# Sheet1.net
KiCad netlist of a schematic drawn in Altium Designer
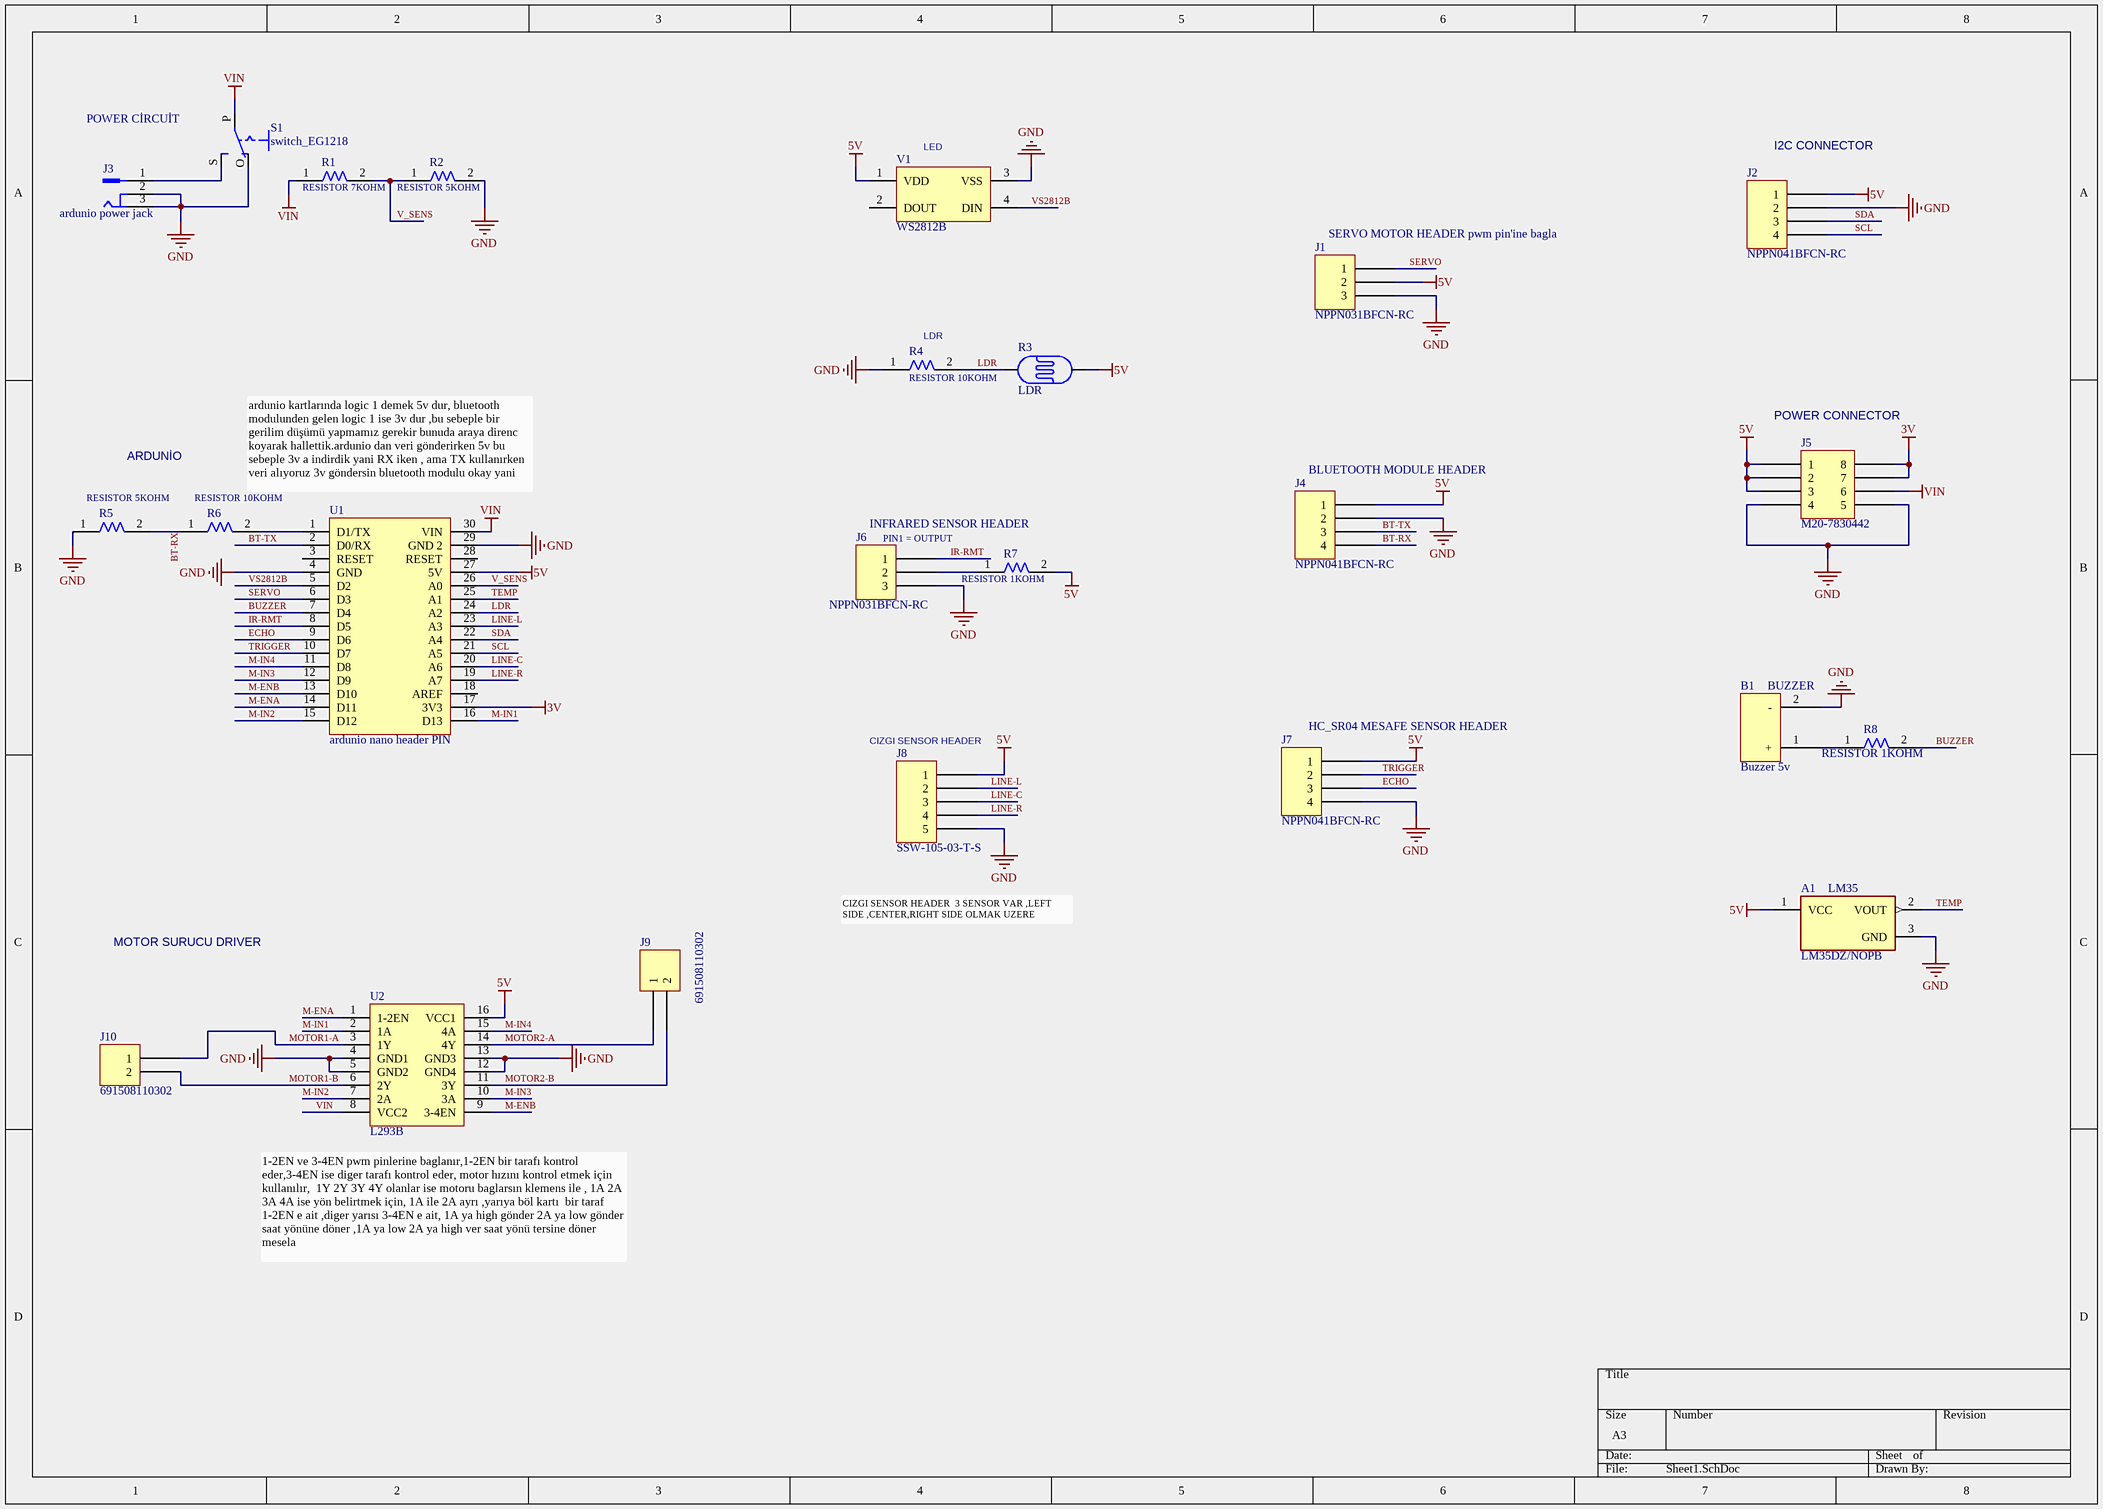
[diagram p0: Sheet1.SchDoc]

(export (version "E")
  (design (tool "Eeschema 10.0.6"))
  (components
    (comp (ref "A1")
      (value "LM35DZ/NOPB")
      (footprint "PcbLib1:LM35DZ_TO92127P521H735-3")
      (description "LM35DZ TEMPERATURE SENSOR")
      (libsource (lib "Schlib1") (part "LM35DZ/NOPB"))
    )
    (comp (ref "B1")
      (value "Buzzer 5v")
      (footprint "Buzzer 5V")
      (libsource (lib "Schlib1") (part "Buzzer 5v"))
    )
    (comp (ref "J1")
      (value "NPPN031BFCN-RC")
      (footprint "SULLINS NPPN031BFCN")
      (description "CONN HDR 3POS 0.079 GOLD PCB")
      (fields (field (name "MANUFACTURER") "Sullins Connector Solutions"))
      (libsource (lib "Celestial Altium Library - altium_library") (part "3 Pin"))
    )
    (comp (ref "J2")
      (value "NPPN041BFCN-RC")
      (footprint "SULLINS NPPN041BFCN")
      (description "CONN HDR 4POS 0.079 GOLD PCB")
      (fields (field (name "MANUFACTURER") "Sullins Connector Solutions"))
      (libsource (lib "Celestial Altium Library - altium_library") (part "4 Pin"))
    )
    (comp (ref "J3")
      (value "ardunio power jack")
      (footprint "ardunio uno power jack")
      (description "CONN PWR JACK 2X5.5MM SOLDER  ,PJ-102AH")
      (libsource (lib "Schlib1") (part "ardunio power jack"))
    )
    (comp (ref "J4")
      (value "NPPN041BFCN-RC")
      (footprint "SULLINS NPPN041BFCN")
      (description "CONN HDR 4POS 0.079 GOLD PCB")
      (fields (field (name "MANUFACTURER") "Sullins Connector Solutions"))
      (libsource (lib "Celestial Altium Library - altium_library") (part "4 Pin"))
    )
    (comp (ref "J5")
      (value "M20-7830442")
      (footprint "HARWIN M20-7830445")
      (description "CONN RCPT 8POS 0.1 GOLD PCB")
      (fields (field (name "MANUFACTURER") "Harwin Inc."))
      (libsource (lib "Celestial Altium Library - altium_library") (part "2X4 PIN DU"))
    )
    (comp (ref "J6")
      (value "NPPN031BFCN-RC")
      (footprint "SULLINS NPPN031BFCN")
      (description "CONN HDR 3POS 0.079 GOLD PCB")
      (fields (field (name "MANUFACTURER") "Sullins Connector Solutions"))
      (libsource (lib "Celestial Altium Library - altium_library") (part "3 Pin"))
    )
    (comp (ref "J7")
      (value "NPPN041BFCN-RC")
      (footprint "SULLINS NPPN041BFCN")
      (description "CONN HDR 4POS 0.079 GOLD PCB")
      (fields (field (name "MANUFACTURER") "Sullins Connector Solutions"))
      (libsource (lib "Celestial Altium Library - altium_library") (part "4 Pin"))
    )
    (comp (ref "J8")
      (value "SSW-105-03-T-S")
      (footprint "SAMTEC SSW-105-03-T-S")
      (description "CONN RCPT 5POS 0.1 TIN PCB")
      (fields (field (name "MANUFACTURER") "Samtec Inc."))
      (libsource (lib "Celestial Altium Library - altium_library") (part "5 Pin"))
    )
    (comp (ref "J9")
      (value "691508110302")
      (footprint "WURTH 691508110302")
      (description "TERM BLOCK 2POS 3.5MM SMD")
      (fields (field (name "MANUFACTURER") "Würth Elektronik") (field (name "VOLTAGE") "300V"))
      (libsource (lib "Celestial Altium Library - altium_library") (part "2 Pin"))
    )
    (comp (ref "J10")
      (value "691508110302")
      (footprint "WURTH 691508110302")
      (description "TERM BLOCK 2POS 3.5MM SMD")
      (fields (field (name "MANUFACTURER") "Würth Elektronik") (field (name "VOLTAGE") "300V"))
      (libsource (lib "") (part "2 Pin_1"))
    )
    (comp (ref "R1")
      (value "RESISTOR 7KOHM")
      (footprint "RES50")
      (libsource (lib "Schlib1") (part "RESISTOR 7KOHM"))
    )
    (comp (ref "R2")
      (value "RESISTOR 5KOHM")
      (footprint "RES50")
      (libsource (lib "Schlib1") (part "RESISTOR 5KOHM"))
    )
    (comp (ref "R3")
      (value "LDR")
      (footprint "PcbLib1:LDR")
      (fields (field (name "MF") "Fairway Electronics"))
      (libsource (lib "Schlib1") (part "LDR"))
    )
    (comp (ref "R4")
      (value "RESISTOR 10KOHM")
      (footprint "RES50")
      (libsource (lib "Schlib1") (part "RESISTOR 10KOHM"))
    )
    (comp (ref "R5")
      (value "RESISTOR 5KOHM")
      (footprint "RES50")
      (libsource (lib "Schlib1") (part "RESISTOR 5KOHM"))
    )
    (comp (ref "R6")
      (value "RESISTOR 10KOHM")
      (footprint "RES50")
      (libsource (lib "Schlib1") (part "RESISTOR 10KOHM"))
    )
    (comp (ref "R7")
      (value "RESISTOR 1KOHM")
      (footprint "RES50")
      (description "RESISTOR 5KOHM")
      (libsource (lib "Schlib1") (part "RESISTOR 5KOHM"))
    )
    (comp (ref "R8")
      (value "RESISTOR 1KOHM")
      (footprint "RES50")
      (description "RESISTOR 5KOHM")
      (libsource (lib "Schlib1") (part "RESISTOR 5KOHM"))
    )
    (comp (ref "S1")
      (value "switch_EG1218")
      (footprint "PcbLib1:EG1218")
      (fields (field (name "MP") "EG1218"))
      (libsource (lib "Schlib1") (part "switch_EG1218"))
    )
    (comp (ref "U1")
      (value "ardunio nano header PIN")
      (footprint "ARDUNIO NANO")
      (description "ardunio nanoheader pin 2x15")
      (libsource (lib "Schlib1") (part "ardunio nanoheader"))
    )
    (comp (ref "U2") (value "L293B") (footprint "L293B-L293D") (libsource (lib "Schlib1") (part "L293B")))
    (comp (ref "V1") (value "WS2812B") (footprint "WS2812B") (libsource (lib "Schlib1") (part "WS2812B")))
  )
  (nets
    (net (code "1") (name "/BT-RX") (class "Default")
      (node (ref "J4") (pin "4") (pinfunction "4_4") (pintype "passive"))
      (node (ref "R5") (pin "2") (pinfunction "2_2") (pintype "passive"))
      (node (ref "R6") (pin "1") (pinfunction "1_1") (pintype "passive"))
    )
    (net (code "2") (name "/BT-TX") (class "Default")
      (node (ref "J4") (pin "3") (pinfunction "3_3") (pintype "passive"))
      (node (ref "U1") (pin "2") (pinfunction "D0/RX_2") (pintype "passive"))
    )
    (net (code "3") (name "/BUZZER") (class "Default")
      (node (ref "R8") (pin "2") (pinfunction "2_2") (pintype "passive"))
      (node (ref "U1") (pin "7") (pinfunction "D4_7") (pintype "passive"))
    )
    (net (code "4") (name "/ECHO") (class "Default")
      (node (ref "J7") (pin "3") (pinfunction "3_3") (pintype "passive"))
      (node (ref "U1") (pin "9") (pinfunction "D6_9") (pintype "passive"))
    )
    (net (code "5") (name "/IR-RMT") (class "Default")
      (node (ref "J6") (pin "1") (pinfunction "1_1") (pintype "passive"))
      (node (ref "U1") (pin "8") (pinfunction "D5_8") (pintype "passive"))
    )
    (net (code "6") (name "/LDR") (class "Default")
      (node (ref "R3") (pin "1") (pinfunction "P$1_1") (pintype "bidirectional"))
      (node (ref "R4") (pin "2") (pinfunction "2_2") (pintype "passive"))
      (node (ref "U1") (pin "24") (pinfunction "A2_24") (pintype "passive"))
    )
    (net (code "7") (name "/LINE-C") (class "Default")
      (node (ref "J8") (pin "3") (pinfunction "3_3") (pintype "passive"))
      (node (ref "U1") (pin "20") (pinfunction "A6_20") (pintype "passive"))
    )
    (net (code "8") (name "/LINE-L") (class "Default")
      (node (ref "J8") (pin "2") (pinfunction "2_2") (pintype "passive"))
      (node (ref "U1") (pin "23") (pinfunction "A3_23") (pintype "passive"))
    )
    (net (code "9") (name "/LINE-R") (class "Default")
      (node (ref "J8") (pin "4") (pinfunction "4_4") (pintype "passive"))
      (node (ref "U1") (pin "19") (pinfunction "A7_19") (pintype "passive"))
    )
    (net (code "10") (name "/M-ENA") (class "Default")
      (node (ref "U1") (pin "14") (pinfunction "D11_14") (pintype "passive"))
      (node (ref "U2") (pin "1") (pinfunction "1-2EN_1") (pintype "passive"))
    )
    (net (code "11") (name "/M-ENB") (class "Default")
      (node (ref "U1") (pin "13") (pinfunction "D10_13") (pintype "passive"))
      (node (ref "U2") (pin "9") (pinfunction "3-4EN_9") (pintype "passive"))
    )
    (net (code "12") (name "/M-IN1") (class "Default")
      (node (ref "U1") (pin "16") (pinfunction "D13_16") (pintype "passive"))
      (node (ref "U2") (pin "2") (pinfunction "1A_2") (pintype "passive"))
    )
    (net (code "13") (name "/M-IN2") (class "Default")
      (node (ref "U1") (pin "15") (pinfunction "D12_15") (pintype "passive"))
      (node (ref "U2") (pin "7") (pinfunction "2A_7") (pintype "passive"))
    )
    (net (code "14") (name "/M-IN3") (class "Default")
      (node (ref "U1") (pin "12") (pinfunction "D9_12") (pintype "passive"))
      (node (ref "U2") (pin "10") (pinfunction "3A_10") (pintype "passive"))
    )
    (net (code "15") (name "/M-IN4") (class "Default")
      (node (ref "U1") (pin "11") (pinfunction "D8_11") (pintype "passive"))
      (node (ref "U2") (pin "15") (pinfunction "4A_15") (pintype "passive"))
    )
    (net (code "16") (name "/MOTOR1-A") (class "Default")
      (node (ref "J10") (pin "1") (pinfunction "1_1") (pintype "passive"))
      (node (ref "U2") (pin "3") (pinfunction "1Y_3") (pintype "passive"))
    )
    (net (code "17") (name "/MOTOR1-B") (class "Default")
      (node (ref "J10") (pin "2") (pinfunction "2_2") (pintype "passive"))
      (node (ref "U2") (pin "6") (pinfunction "2Y_6") (pintype "passive"))
    )
    (net (code "18") (name "/MOTOR2-A") (class "Default")
      (node (ref "J9") (pin "1") (pinfunction "1_1") (pintype "passive"))
      (node (ref "U2") (pin "14") (pinfunction "4Y_14") (pintype "passive"))
    )
    (net (code "19") (name "/MOTOR2-B") (class "Default")
      (node (ref "J9") (pin "2") (pinfunction "2_2") (pintype "passive"))
      (node (ref "U2") (pin "11") (pinfunction "3Y_11") (pintype "passive"))
    )
    (net (code "20") (name "/SCL") (class "Default")
      (node (ref "J2") (pin "4") (pinfunction "4_4") (pintype "passive"))
      (node (ref "U1") (pin "21") (pinfunction "A5_21") (pintype "passive"))
    )
    (net (code "21") (name "/SDA") (class "Default")
      (node (ref "J2") (pin "3") (pinfunction "3_3") (pintype "passive"))
      (node (ref "U1") (pin "22") (pinfunction "A4_22") (pintype "passive"))
    )
    (net (code "22") (name "/SERVO") (class "Default")
      (node (ref "J1") (pin "1") (pinfunction "1_1") (pintype "passive"))
      (node (ref "U1") (pin "6") (pinfunction "D3_6") (pintype "passive"))
    )
    (net (code "23") (name "/TEMP") (class "Default")
      (node (ref "A1") (pin "2") (pinfunction "VOUT_2") (pintype "output"))
      (node (ref "U1") (pin "25") (pinfunction "A1_25") (pintype "passive"))
    )
    (net (code "24") (name "/TRIGGER") (class "Default")
      (node (ref "J7") (pin "2") (pinfunction "2_2") (pintype "passive"))
      (node (ref "U1") (pin "10") (pinfunction "D7_10") (pintype "passive"))
    )
    (net (code "25") (name "/VS2812B") (class "Default")
      (node (ref "U1") (pin "5") (pinfunction "D2_5") (pintype "passive"))
      (node (ref "V1") (pin "4") (pinfunction "DIN_4") (pintype "passive"))
    )
    (net (code "26") (name "/V_SENS") (class "Default")
      (node (ref "R1") (pin "2") (pinfunction "2_2") (pintype "passive"))
      (node (ref "R2") (pin "1") (pinfunction "1_1") (pintype "passive"))
      (node (ref "U1") (pin "26") (pinfunction "A0_26") (pintype "passive"))
    )
    (net (code "27") (name "3V") (class "Default")
      (node (ref "J5") (pin "7") (pinfunction "7_7") (pintype "passive"))
      (node (ref "J5") (pin "8") (pinfunction "8_8") (pintype "passive"))
      (node (ref "U1") (pin "17") (pinfunction "3V3_17") (pintype "passive"))
    )
    (net (code "28") (name "5V") (class "Default")
      (node (ref "A1") (pin "1") (pinfunction "VCC_1") (pintype "power_in"))
      (node (ref "J1") (pin "2") (pinfunction "2_2") (pintype "passive"))
      (node (ref "J2") (pin "1") (pinfunction "1_1") (pintype "passive"))
      (node (ref "J4") (pin "1") (pinfunction "1_1") (pintype "passive"))
      (node (ref "J5") (pin "1") (pinfunction "1_1") (pintype "passive"))
      (node (ref "J5") (pin "2") (pinfunction "2_2") (pintype "passive"))
      (node (ref "J5") (pin "3") (pinfunction "3_3") (pintype "passive"))
      (node (ref "J7") (pin "1") (pinfunction "1_1") (pintype "passive"))
      (node (ref "J8") (pin "1") (pinfunction "1_1") (pintype "passive"))
      (node (ref "R3") (pin "2") (pinfunction "P$2_2") (pintype "bidirectional"))
      (node (ref "R7") (pin "2") (pinfunction "2_2") (pintype "passive"))
      (node (ref "U1") (pin "27") (pinfunction "5V_27") (pintype "passive"))
      (node (ref "U2") (pin "16") (pinfunction "VCC1_16") (pintype "passive"))
      (node (ref "V1") (pin "1") (pinfunction "VDD_1") (pintype "passive"))
    )
    (net (code "29") (name "GND") (class "Default")
      (node (ref "A1") (pin "3") (pinfunction "GND_3") (pintype "power_in"))
      (node (ref "B1") (pin "2") (pinfunction "-_2") (pintype "passive"))
      (node (ref "J1") (pin "3") (pinfunction "3_3") (pintype "passive"))
      (node (ref "J2") (pin "2") (pinfunction "2_2") (pintype "passive"))
      (node (ref "J3") (pin "2") (pinfunction "2_2") (pintype "passive"))
      (node (ref "J3") (pin "3") (pinfunction "3_3") (pintype "passive"))
      (node (ref "J4") (pin "2") (pinfunction "2_2") (pintype "passive"))
      (node (ref "J5") (pin "4") (pinfunction "4_4") (pintype "passive"))
      (node (ref "J5") (pin "5") (pinfunction "5_5") (pintype "passive"))
      (node (ref "J6") (pin "3") (pinfunction "3_3") (pintype "passive"))
      (node (ref "J7") (pin "4") (pinfunction "4_4") (pintype "passive"))
      (node (ref "J8") (pin "5") (pinfunction "5_5") (pintype "passive"))
      (node (ref "R2") (pin "2") (pinfunction "2_2") (pintype "passive"))
      (node (ref "R4") (pin "1") (pinfunction "1_1") (pintype "passive"))
      (node (ref "R5") (pin "1") (pinfunction "1_1") (pintype "passive"))
      (node (ref "S1") (pin "O") (pinfunction "O_O") (pintype "passive"))
      (node (ref "U1") (pin "29") (pinfunction "GND_2_29") (pintype "passive"))
      (node (ref "U1") (pin "4") (pinfunction "GND_4") (pintype "passive"))
      (node (ref "U2") (pin "12") (pinfunction "GND4_12") (pintype "passive"))
      (node (ref "U2") (pin "13") (pinfunction "GND3_13") (pintype "passive"))
      (node (ref "U2") (pin "4") (pinfunction "GND1_4") (pintype "passive"))
      (node (ref "U2") (pin "5") (pinfunction "GND2_5") (pintype "passive"))
      (node (ref "V1") (pin "3") (pinfunction "VSS_3") (pintype "passive"))
    )
    (net (code "30") (name "Net-(B1-+)") (class "Default")
      (node (ref "B1") (pin "1") (pinfunction "+_1") (pintype "passive"))
      (node (ref "R8") (pin "1") (pinfunction "1_1") (pintype "passive"))
    )
    (net (code "31") (name "Net-(J3-Pad1)") (class "Default")
      (node (ref "J3") (pin "1") (pinfunction "1_1") (pintype "passive"))
      (node (ref "S1") (pin "S") (pinfunction "S_S") (pintype "passive"))
    )
    (net (code "32") (name "Net-(J6-Pad2)") (class "Default")
      (node (ref "J6") (pin "2") (pinfunction "2_2") (pintype "passive"))
      (node (ref "R7") (pin "1") (pinfunction "1_1") (pintype "passive"))
    )
    (net (code "33") (name "Net-(U1-D1{slash}TX)") (class "Default")
      (node (ref "R6") (pin "2") (pinfunction "2_2") (pintype "passive"))
      (node (ref "U1") (pin "1") (pinfunction "D1/TX_1") (pintype "passive"))
    )
    (net (code "34") (name "VIN") (class "Default")
      (node (ref "J5") (pin "6") (pinfunction "6_6") (pintype "passive"))
      (node (ref "R1") (pin "1") (pinfunction "1_1") (pintype "passive"))
      (node (ref "S1") (pin "P") (pinfunction "P_P") (pintype "passive"))
      (node (ref "U1") (pin "30") (pinfunction "VIN_30") (pintype "passive"))
      (node (ref "U2") (pin "8") (pinfunction "VCC2_8") (pintype "passive"))
    )
    (net (code "35") (name "unconnected-(U1-AREF-Pad18)") (class "Default")
      (node (ref "U1") (pin "18") (pinfunction "AREF_18") (pintype "passive"))
    )
    (net (code "36") (name "unconnected-(U1-RESET-Pad3)") (class "Default")
      (node (ref "U1") (pin "3") (pinfunction "RESET_3") (pintype "passive"))
    )
    (net (code "37") (name "unconnected-(U1-RESET-Pad28)") (class "Default")
      (node (ref "U1") (pin "28") (pinfunction "RESET_28") (pintype "passive"))
    )
    (net (code "38") (name "unconnected-(V1-DOUT-Pad2)") (class "Default")
      (node (ref "V1") (pin "2") (pinfunction "DOUT_2") (pintype "passive"))
    )
  )
)
